# Adafruit_HTU21D-F_STEMMA_QT.net
KiCad netlist of a schematic drawn in EAGLE
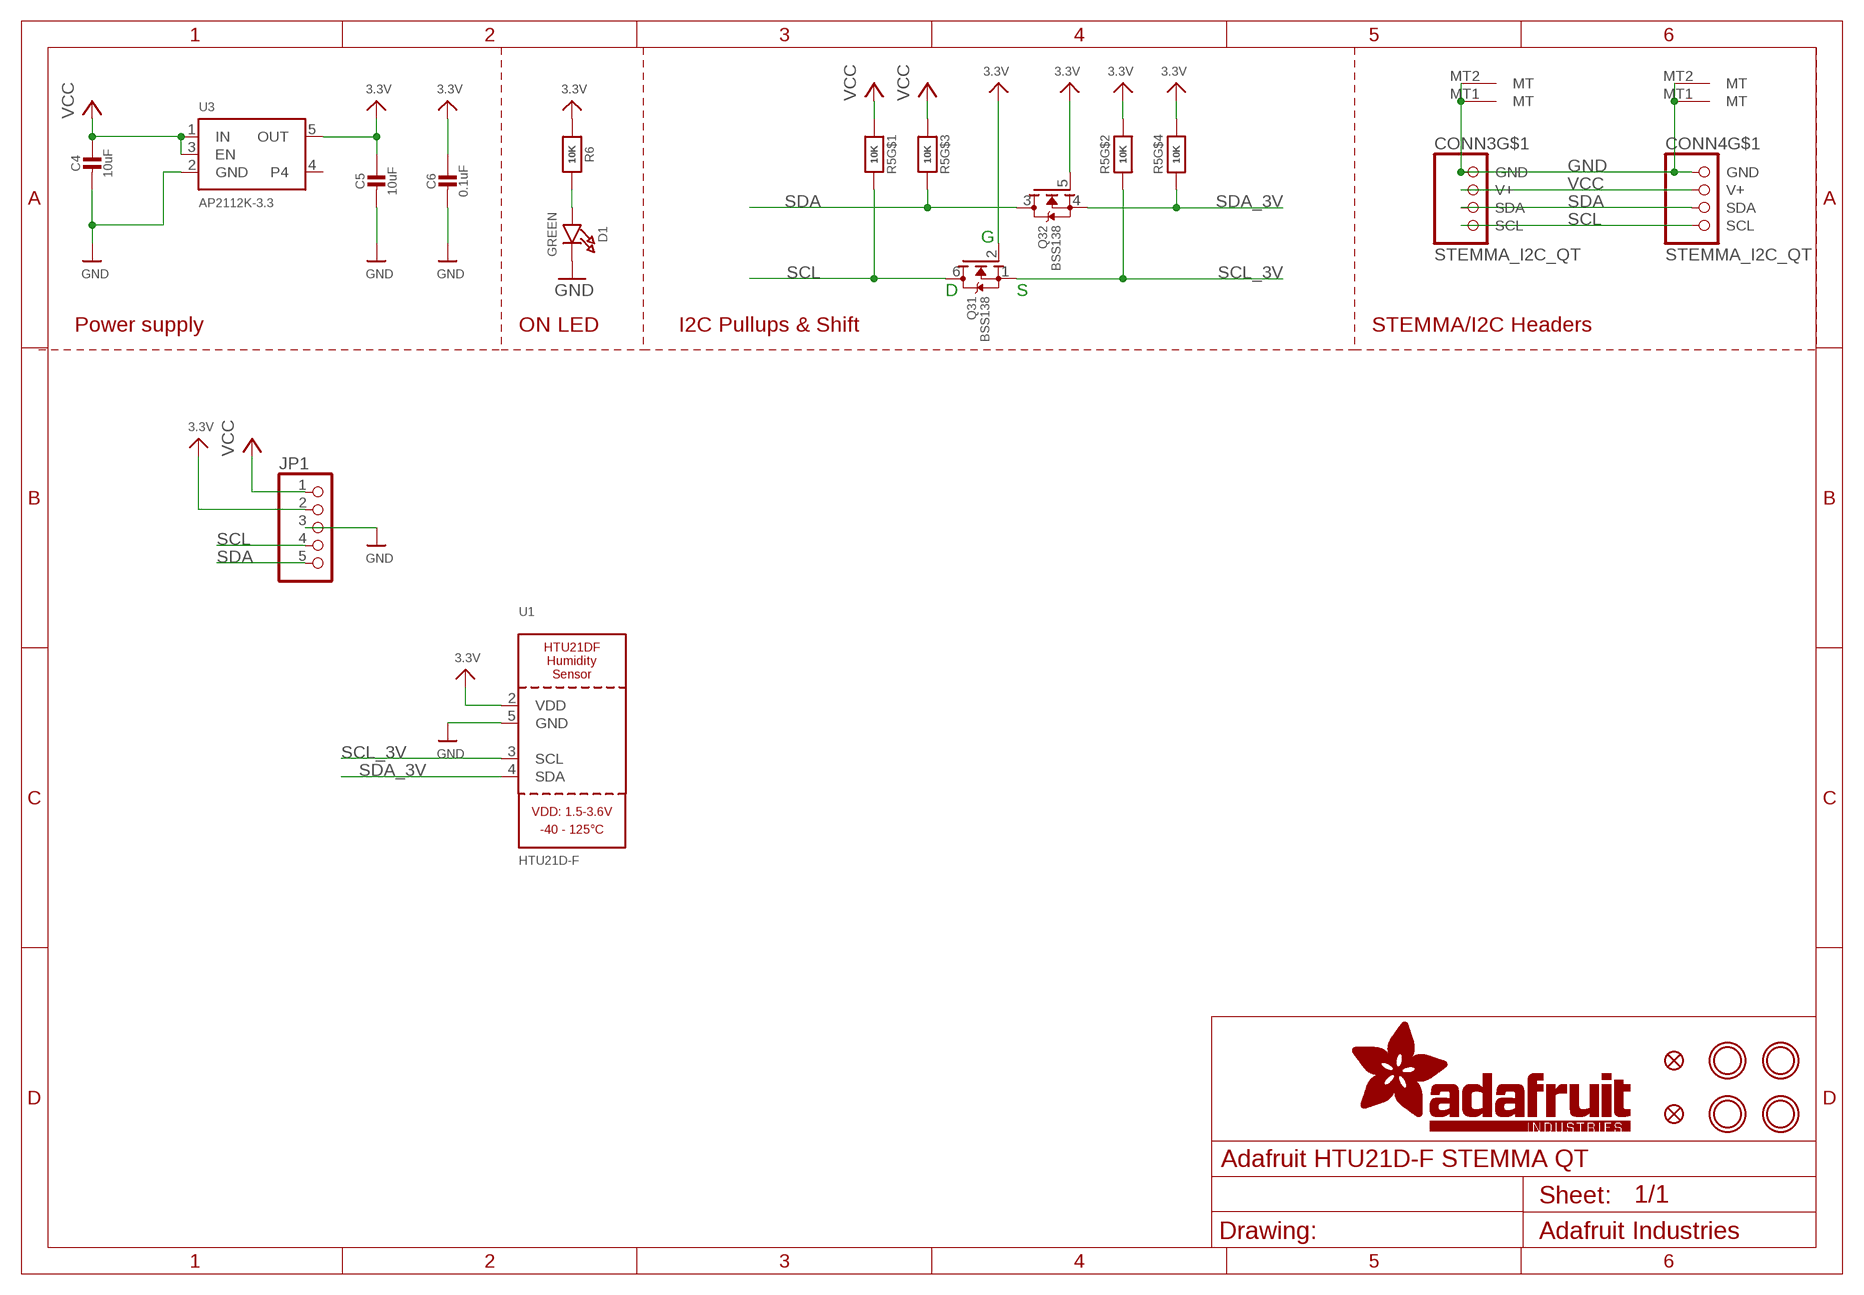
[diagram p0: schematic, sheet 1]

(export (version "E")
  (design (tool "Eeschema 10.0.6"))
  (components
    (comp (ref "C4")
      (value "10uF")
      (footprint "eagle-import:0805-NO")
      (libsource (lib "eagle-import") (part "CAP_CERAMIC0805-NOOUTLINE"))
    )
    (comp (ref "C5")
      (value "10uF")
      (footprint "eagle-import:0805-NO")
      (libsource (lib "eagle-import") (part "CAP_CERAMIC0805-NOOUTLINE"))
    )
    (comp (ref "C6")
      (value "0.1uF")
      (footprint "eagle-import:0603-NO")
      (libsource (lib "eagle-import") (part "CAP_CERAMIC0603_NO"))
    )
    (comp (ref "CONN3")
      (value "STEMMA_I2C_QT")
      (footprint "eagle-import:JST_SH4")
      (libsource (lib "eagle-import") (part "STEMMA_I2C_QT"))
    )
    (comp (ref "CONN4")
      (value "STEMMA_I2C_QT")
      (footprint "eagle-import:JST_SH4")
      (libsource (lib "eagle-import") (part "STEMMA_I2C_QT"))
    )
    (comp (ref "D1")
      (value "GREEN")
      (footprint "eagle-import:CHIPLED_0603_NOOUTLINE")
      (libsource (lib "eagle-import") (part "LED0603_NOOUTLINE"))
    )
    (comp (ref "FID3")
      (value "FIDUCIAL_1MM")
      (footprint "eagle-import:FIDUCIAL_1MM")
      (libsource (lib "eagle-import") (part "FIDUCIAL_1MM"))
    )
    (comp (ref "FID4")
      (value "FIDUCIAL_1MM")
      (footprint "eagle-import:FIDUCIAL_1MM")
      (libsource (lib "eagle-import") (part "FIDUCIAL_1MM"))
    )
    (comp (ref "JP1")
      (value "HEADER-1X570MIL")
      (footprint "eagle-import:1X05_ROUND_70")
      (libsource (lib "eagle-import") (part "HEADER-1X570MIL"))
    )
    (comp (ref "Q3")
      (value "BSS138")
      (footprint "eagle-import:SOT363")
      (libsource (lib "eagle-import") (part "MOSFET-N_DUAL"))
    )
    (comp (ref "R5")
      (value "10K")
      (footprint "eagle-import:RESPACK_4X0603")
      (libsource (lib "eagle-import") (part "RESISTOR_4PACK"))
    )
    (comp (ref "R6")
      (value "10K")
      (footprint "eagle-import:0603-NO")
      (libsource (lib "eagle-import") (part "RESISTOR_0603_NOOUT"))
    )
    (comp (ref "U$19")
      (value "MOUNTINGHOLE2.5")
      (footprint "eagle-import:MOUNTINGHOLE_2.5_PLATED")
      (libsource (lib "eagle-import") (part "MOUNTINGHOLE2.5"))
    )
    (comp (ref "U$20")
      (value "MOUNTINGHOLE2.5")
      (footprint "eagle-import:MOUNTINGHOLE_2.5_PLATED")
      (libsource (lib "eagle-import") (part "MOUNTINGHOLE2.5"))
    )
    (comp (ref "U$22")
      (value "MOUNTINGHOLE2.5")
      (footprint "eagle-import:MOUNTINGHOLE_2.5_PLATED")
      (libsource (lib "eagle-import") (part "MOUNTINGHOLE2.5"))
    )
    (comp (ref "U$25")
      (value "MOUNTINGHOLE2.5")
      (footprint "eagle-import:MOUNTINGHOLE_2.5_PLATED")
      (libsource (lib "eagle-import") (part "MOUNTINGHOLE2.5"))
    )
    (comp (ref "U1")
      (value "HTU21D-F")
      (footprint "eagle-import:HTU21DF")
      (libsource (lib "eagle-import") (part "HTU21DF"))
    )
    (comp (ref "U3")
      (value "AP2112K-3.3")
      (footprint "eagle-import:SOT23-5")
      (libsource (lib "eagle-import") (part "VREG_SOT23-5"))
    )
  )
  (nets
    (net (code "1") (name "/SCL") (class "Default")
      (node (ref "CONN3") (pin "4") (pinfunction "SCL_4") (pintype "passive"))
      (node (ref "CONN4") (pin "4") (pinfunction "SCL_4") (pintype "passive"))
      (node (ref "JP1") (pin "4") (pinfunction "4_4") (pintype "passive"))
      (node (ref "Q3") (pin "6") (pinfunction "D_6") (pintype "bidirectional"))
      (node (ref "R5") (pin "8") (pinfunction "2_8") (pintype "passive"))
    )
    (net (code "2") (name "/SCL_3V") (class "Default")
      (node (ref "Q3") (pin "1") (pinfunction "S_1") (pintype "bidirectional"))
      (node (ref "R5") (pin "7") (pinfunction "2_7") (pintype "passive"))
      (node (ref "U1") (pin "3") (pinfunction "SCL_3") (pintype "input"))
    )
    (net (code "3") (name "/SDA") (class "Default")
      (node (ref "CONN3") (pin "3") (pinfunction "SDA_3") (pintype "passive"))
      (node (ref "CONN4") (pin "3") (pinfunction "SDA_3") (pintype "passive"))
      (node (ref "JP1") (pin "5") (pinfunction "5_5") (pintype "passive"))
      (node (ref "Q3") (pin "3") (pinfunction "D_3") (pintype "bidirectional"))
      (node (ref "R5") (pin "6") (pinfunction "2_6") (pintype "passive"))
    )
    (net (code "4") (name "/SDA_3V") (class "Default")
      (node (ref "Q3") (pin "4") (pinfunction "S_4") (pintype "bidirectional"))
      (node (ref "R5") (pin "5") (pinfunction "2_5") (pintype "passive"))
      (node (ref "U1") (pin "4") (pinfunction "SDA_4") (pintype "bidirectional"))
    )
    (net (code "5") (name "3.3V") (class "Default")
      (node (ref "C5") (pin "1") (pinfunction "1_1") (pintype "passive"))
      (node (ref "C6") (pin "1") (pinfunction "1_1") (pintype "passive"))
      (node (ref "JP1") (pin "2") (pinfunction "2_2") (pintype "passive"))
      (node (ref "Q3") (pin "2") (pinfunction "G_2") (pintype "bidirectional"))
      (node (ref "Q3") (pin "5") (pinfunction "G_5") (pintype "bidirectional"))
      (node (ref "R5") (pin "2") (pinfunction "1_2") (pintype "passive"))
      (node (ref "R5") (pin "4") (pinfunction "1_4") (pintype "passive"))
      (node (ref "R6") (pin "1") (pinfunction "1_1") (pintype "passive"))
      (node (ref "U1") (pin "2") (pinfunction "VDD_2") (pintype "power_in"))
      (node (ref "U3") (pin "5") (pinfunction "OUT_5") (pintype "power_in"))
    )
    (net (code "6") (name "GND") (class "Default")
      (node (ref "C4") (pin "2") (pinfunction "2_2") (pintype "passive"))
      (node (ref "C5") (pin "2") (pinfunction "2_2") (pintype "passive"))
      (node (ref "C6") (pin "2") (pinfunction "2_2") (pintype "passive"))
      (node (ref "CONN3") (pin "1") (pinfunction "GND_1") (pintype "passive"))
      (node (ref "CONN3") (pin "MT1") (pinfunction "MT_MT1") (pintype "bidirectional"))
      (node (ref "CONN3") (pin "MT2") (pinfunction "MT_MT2") (pintype "bidirectional"))
      (node (ref "CONN4") (pin "1") (pinfunction "GND_1") (pintype "passive"))
      (node (ref "CONN4") (pin "MT1") (pinfunction "MT_MT1") (pintype "bidirectional"))
      (node (ref "CONN4") (pin "MT2") (pinfunction "MT_MT2") (pintype "bidirectional"))
      (node (ref "D1") (pin "C") (pinfunction "C_C") (pintype "passive"))
      (node (ref "JP1") (pin "3") (pinfunction "3_3") (pintype "passive"))
      (node (ref "U1") (pin "5") (pinfunction "GND_5") (pintype "power_in"))
      (node (ref "U3") (pin "2") (pinfunction "GND_2") (pintype "power_in"))
    )
    (net (code "7") (name "Net-(D1-PadA)") (class "Default")
      (node (ref "D1") (pin "A") (pinfunction "A_A") (pintype "passive"))
      (node (ref "R6") (pin "2") (pinfunction "2_2") (pintype "passive"))
    )
    (net (code "8") (name "VCC") (class "Default")
      (node (ref "C4") (pin "1") (pinfunction "1_1") (pintype "passive"))
      (node (ref "CONN3") (pin "2") (pinfunction "V+_2") (pintype "passive"))
      (node (ref "CONN4") (pin "2") (pinfunction "V+_2") (pintype "passive"))
      (node (ref "JP1") (pin "1") (pinfunction "1_1") (pintype "passive"))
      (node (ref "R5") (pin "1") (pinfunction "1_1") (pintype "passive"))
      (node (ref "R5") (pin "3") (pinfunction "1_3") (pintype "passive"))
      (node (ref "U3") (pin "1") (pinfunction "IN_1") (pintype "power_in"))
      (node (ref "U3") (pin "3") (pinfunction "EN_3") (pintype "input"))
    )
    (net (code "9") (name "unconnected-(U3-P4-Pad4)") (class "Default")
      (node (ref "U3") (pin "4") (pinfunction "P4_4") (pintype "bidirectional"))
    )
  )
)
